# Sheet3.net
KiCad netlist of a schematic drawn in Altium Designer
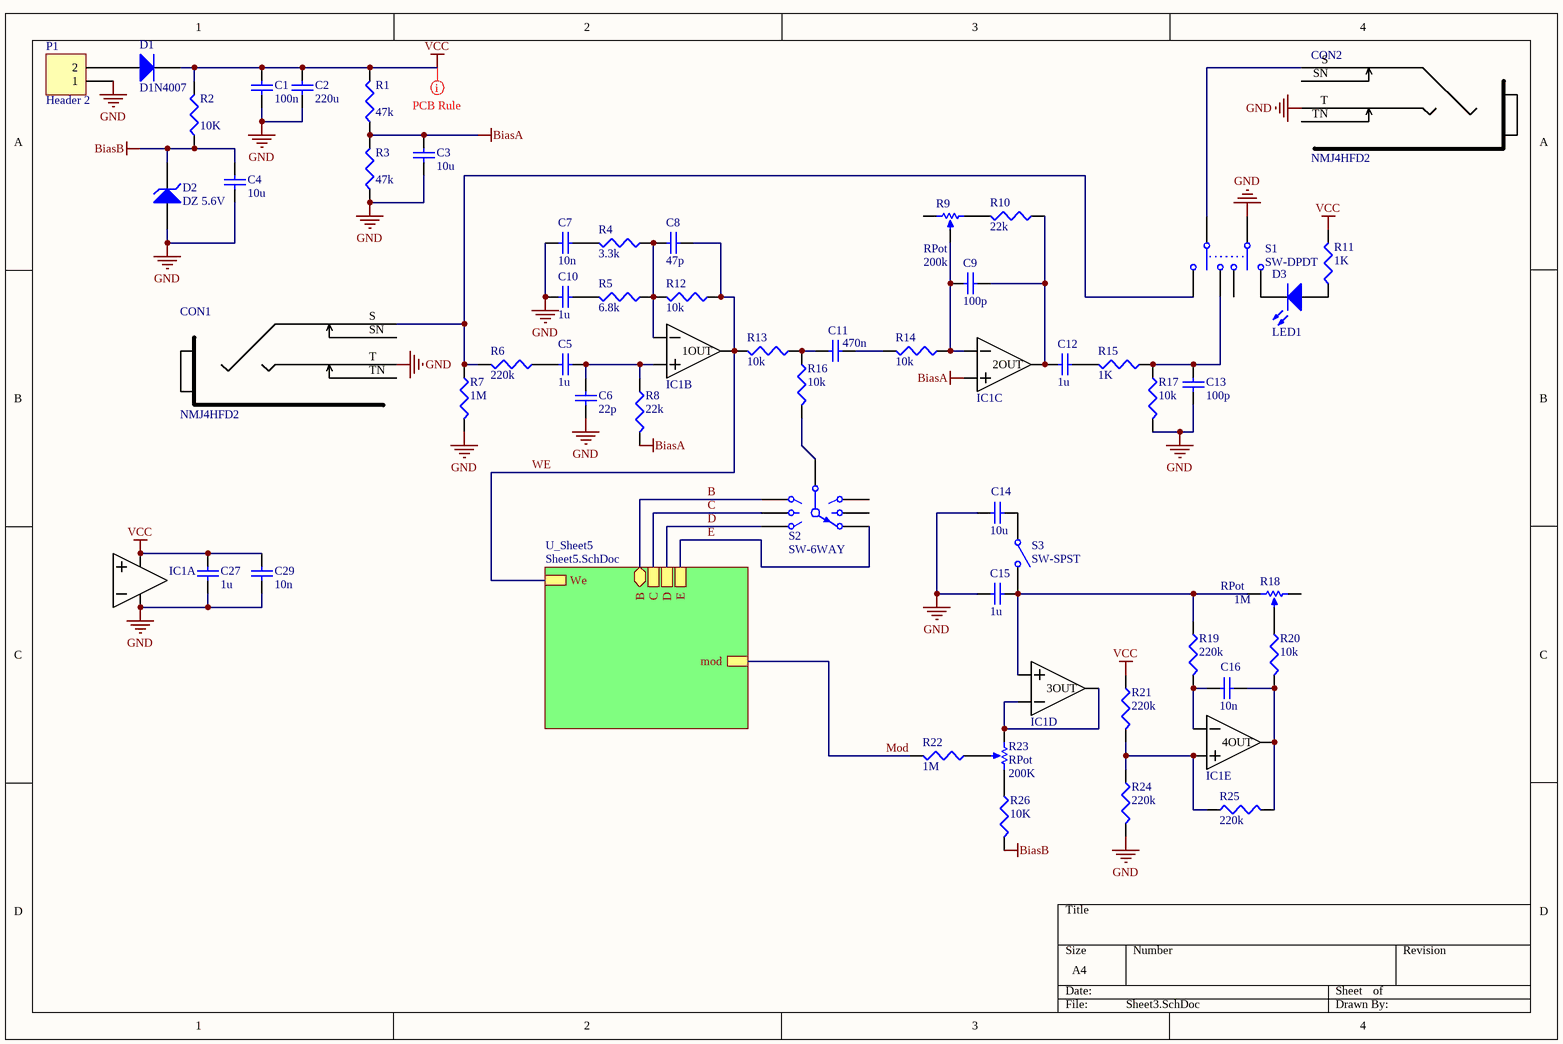
[diagram p0: Sheet3.SchDoc]

(export (version "E")
  (design (tool "Eeschema 10.0.6"))
  (components
    (comp (ref "C1")
      (value "100n")
      (footprint "C1206")
      (description "Capacitor (Semiconductor SIM Model)")
      (fields (field (name "Comment") "Cap Semi") (field (name "PUBLISHER") "Altium Limited"))
      (libsource (lib "Miscellaneous Devices") (part "Cap Semi"))
    )
    (comp (ref "C2")
      (value "220u")
      (footprint "C1206")
      (description "Capacitor (Semiconductor SIM Model)")
      (fields (field (name "Comment") "Cap Semi") (field (name "PUBLISHER") "Altium Limited"))
      (libsource (lib "Miscellaneous Devices") (part "Cap Semi"))
    )
    (comp (ref "C3")
      (value "10u")
      (footprint "C1206")
      (description "Capacitor (Semiconductor SIM Model)")
      (fields (field (name "Comment") "Cap Semi") (field (name "PUBLISHER") "Altium Limited"))
      (libsource (lib "Miscellaneous Devices") (part "Cap Semi"))
    )
    (comp (ref "C4")
      (value "10u")
      (footprint "C1206")
      (description "Capacitor (Semiconductor SIM Model)")
      (fields (field (name "Comment") "Cap Semi") (field (name "PUBLISHER") "Altium Limited"))
      (libsource (lib "Miscellaneous Devices") (part "Cap Semi"))
    )
    (comp (ref "C5")
      (value "1u")
      (footprint "C1206")
      (description "Capacitor (Semiconductor SIM Model)")
      (fields (field (name "Comment") "Cap Semi") (field (name "PUBLISHER") "Altium Limited"))
      (libsource (lib "Miscellaneous Devices") (part "Cap Semi"))
    )
    (comp (ref "C6")
      (value "22p")
      (footprint "C1206")
      (description "Capacitor (Semiconductor SIM Model)")
      (fields (field (name "Comment") "Cap Semi") (field (name "PUBLISHER") "Altium Limited"))
      (libsource (lib "Miscellaneous Devices") (part "Cap Semi"))
    )
    (comp (ref "C7")
      (value "10n")
      (footprint "C1206")
      (description "Capacitor (Semiconductor SIM Model)")
      (fields (field (name "Comment") "Cap Semi") (field (name "PUBLISHER") "Altium Limited"))
      (libsource (lib "Miscellaneous Devices") (part "Cap Semi"))
    )
    (comp (ref "C8")
      (value "47p")
      (footprint "C1206")
      (description "Capacitor (Semiconductor SIM Model)")
      (fields (field (name "Comment") "Cap Semi") (field (name "PUBLISHER") "Altium Limited"))
      (libsource (lib "Miscellaneous Devices") (part "Cap Semi"))
    )
    (comp (ref "C9")
      (value "100p")
      (footprint "C1206")
      (description "Capacitor (Semiconductor SIM Model)")
      (fields (field (name "Comment") "Cap Semi") (field (name "PUBLISHER") "Altium Limited"))
      (libsource (lib "Miscellaneous Devices") (part "Cap Semi"))
    )
    (comp (ref "C10")
      (value "1u")
      (footprint "C1206")
      (description "Capacitor (Semiconductor SIM Model)")
      (fields (field (name "Comment") "Cap Semi") (field (name "PUBLISHER") "Altium Limited"))
      (libsource (lib "Miscellaneous Devices") (part "Cap Semi"))
    )
    (comp (ref "C11")
      (value "470n")
      (footprint "C1206")
      (description "Capacitor (Semiconductor SIM Model)")
      (fields (field (name "Comment") "Cap Semi") (field (name "PUBLISHER") "Altium Limited"))
      (libsource (lib "Miscellaneous Devices") (part "Cap Semi"))
    )
    (comp (ref "C12")
      (value "1u")
      (footprint "C1206")
      (description "Capacitor (Semiconductor SIM Model)")
      (fields (field (name "Comment") "Cap Semi") (field (name "PUBLISHER") "Altium Limited"))
      (libsource (lib "Miscellaneous Devices") (part "Cap Semi"))
    )
    (comp (ref "C13")
      (value "100p")
      (footprint "C1206")
      (description "Capacitor (Semiconductor SIM Model)")
      (fields (field (name "Comment") "Cap Semi") (field (name "PUBLISHER") "Altium Limited"))
      (libsource (lib "Miscellaneous Devices") (part "Cap Semi"))
    )
    (comp (ref "C14")
      (value "10u")
      (footprint "C1206")
      (description "Capacitor (Semiconductor SIM Model)")
      (fields (field (name "Comment") "Cap Semi") (field (name "PUBLISHER") "Altium Limited"))
      (libsource (lib "Miscellaneous Devices") (part "Cap Semi"))
    )
    (comp (ref "C15")
      (value "1u")
      (footprint "C1206")
      (description "Capacitor (Semiconductor SIM Model)")
      (fields (field (name "Comment") "Cap Semi") (field (name "PUBLISHER") "Altium Limited"))
      (libsource (lib "Miscellaneous Devices") (part "Cap Semi"))
    )
    (comp (ref "C16")
      (value "10n")
      (footprint "C1206")
      (description "Capacitor (Semiconductor SIM Model)")
      (fields (field (name "Comment") "Cap Semi") (field (name "PUBLISHER") "Altium Limited"))
      (libsource (lib "Miscellaneous Devices") (part "Cap Semi"))
    )
    (comp (ref "C27")
      (value "1u")
      (footprint "C1206")
      (description "Capacitor (Semiconductor SIM Model)")
      (fields (field (name "Comment") "Cap Semi") (field (name "PUBLISHER") "Altium Limited"))
      (libsource (lib "Miscellaneous Devices") (part "Cap Semi"))
    )
    (comp (ref "C29")
      (value "10n")
      (footprint "C1206")
      (description "Capacitor (Semiconductor SIM Model)")
      (fields (field (name "Comment") "Cap Semi") (field (name "PUBLISHER") "Altium Limited"))
      (libsource (lib "Miscellaneous Devices") (part "Cap Semi"))
    )
    (comp (ref "CON1")
      (value "NMJ4HFD2")
      (footprint "NMJ4HFD2")
      (description "1/4\" jack connector")
      (libsource (lib "lib1") (part "NMJ4HFD2"))
    )
    (comp (ref "CON2")
      (value "NMJ4HFD2")
      (footprint "NMJ4HFD2")
      (description "1/4\" jack connector")
      (libsource (lib "lib1") (part "NMJ4HFD2"))
    )
    (comp (ref "D1")
      (value "D1N4007")
      (footprint "DO-41")
      (description "1 Amp General Purpose Rectifier")
      (fields (field (name "PUBLISHER") "Altium Limited"))
      (libsource (lib "Miscellaneous Devices") (part "Diode 1N4007"))
    )
    (comp (ref "D2")
      (value "DZ 5.6V")
      (footprint "DIODE-0.7")
      (description "Zener Diode")
      (fields (field (name "PUBLISHER") "Altium Limited"))
      (libsource (lib "Miscellaneous Devices") (part "D Zener"))
    )
    (comp (ref "D3")
      (value "LED1")
      (footprint "LED-1")
      (description "Typical RED GaAs LED")
      (fields (field (name "PUBLISHER") "Altium Limited"))
      (libsource (lib "Miscellaneous Devices") (part "LED1"))
    )
    (comp (ref "IC1")
      (value "TL074A")
      (footprint "TL074A")
      (description "TL074A Op-Amp")
      (libsource (lib "lib1") (part "TL074A"))
    )
    (comp (ref "P1")
      (value "Header 2")
      (footprint "HDR1X2")
      (description "Header, 2-Pin")
      (fields (field (name "PUBLISHER") "Altium Limited"))
      (libsource (lib "Miscellaneous Connectors") (part "Header 2"))
    )
    (comp (ref "R1")
      (value "47k")
      (footprint "J1-0603")
      (description "Resistor")
      (fields (field (name "Comment") "Res3") (field (name "PUBLISHER") "Altium Limited"))
      (libsource (lib "Miscellaneous Devices") (part "Res3"))
    )
    (comp (ref "R2")
      (value "10K")
      (footprint "J1-0603")
      (description "Resistor")
      (fields (field (name "Comment") "Res3") (field (name "PUBLISHER") "Altium Limited"))
      (libsource (lib "Miscellaneous Devices") (part "Res3"))
    )
    (comp (ref "R3")
      (value "47k")
      (footprint "J1-0603")
      (description "Resistor")
      (fields (field (name "Comment") "Res3") (field (name "PUBLISHER") "Altium Limited"))
      (libsource (lib "Miscellaneous Devices") (part "Res3"))
    )
    (comp (ref "R4")
      (value "3.3k")
      (footprint "J1-0603")
      (description "Resistor")
      (fields (field (name "Comment") "Res3") (field (name "PUBLISHER") "Altium Limited"))
      (libsource (lib "Miscellaneous Devices") (part "Res3"))
    )
    (comp (ref "R5")
      (value "6.8k")
      (footprint "J1-0603")
      (description "Resistor")
      (fields (field (name "Comment") "Res3") (field (name "PUBLISHER") "Altium Limited"))
      (libsource (lib "Miscellaneous Devices") (part "Res3"))
    )
    (comp (ref "R6")
      (value "220k")
      (footprint "J1-0603")
      (description "Resistor")
      (fields (field (name "Comment") "Res3") (field (name "PUBLISHER") "Altium Limited"))
      (libsource (lib "Miscellaneous Devices") (part "Res3"))
    )
    (comp (ref "R7")
      (value "1M")
      (footprint "J1-0603")
      (description "Resistor")
      (fields (field (name "Comment") "Res3") (field (name "PUBLISHER") "Altium Limited"))
      (libsource (lib "Miscellaneous Devices") (part "Res3"))
    )
    (comp (ref "R8")
      (value "22k")
      (footprint "J1-0603")
      (description "Resistor")
      (fields (field (name "Comment") "Res3") (field (name "PUBLISHER") "Altium Limited"))
      (libsource (lib "Miscellaneous Devices") (part "Res3"))
    )
    (comp (ref "R9")
      (value "RPot")
      (footprint "VR5")
      (description "Potentiometer")
      (fields (field (name "ALTIUM_VALUE") "200k") (field (name "PUBLISHER") "Altium Limited"))
      (libsource (lib "Miscellaneous Devices") (part "RPot"))
    )
    (comp (ref "R10")
      (value "22k")
      (footprint "J1-0603")
      (description "Resistor")
      (fields (field (name "Comment") "Res3") (field (name "PUBLISHER") "Altium Limited"))
      (libsource (lib "Miscellaneous Devices") (part "Res3"))
    )
    (comp (ref "R11")
      (value "1K")
      (footprint "J1-0603")
      (description "Resistor")
      (fields (field (name "Comment") "Res3") (field (name "PUBLISHER") "Altium Limited"))
      (libsource (lib "Miscellaneous Devices") (part "Res3"))
    )
    (comp (ref "R12")
      (value "10k")
      (footprint "J1-0603")
      (description "Resistor")
      (fields (field (name "Comment") "Res3") (field (name "PUBLISHER") "Altium Limited"))
      (libsource (lib "Miscellaneous Devices") (part "Res3"))
    )
    (comp (ref "R13")
      (value "10k")
      (footprint "J1-0603")
      (description "Resistor")
      (fields (field (name "Comment") "Res3") (field (name "PUBLISHER") "Altium Limited"))
      (libsource (lib "Miscellaneous Devices") (part "Res3"))
    )
    (comp (ref "R14")
      (value "10k")
      (footprint "J1-0603")
      (description "Resistor")
      (fields (field (name "Comment") "Res3") (field (name "PUBLISHER") "Altium Limited"))
      (libsource (lib "Miscellaneous Devices") (part "Res3"))
    )
    (comp (ref "R15")
      (value "1K")
      (footprint "J1-0603")
      (description "Resistor")
      (fields (field (name "Comment") "Res3") (field (name "PUBLISHER") "Altium Limited"))
      (libsource (lib "Miscellaneous Devices") (part "Res3"))
    )
    (comp (ref "R16")
      (value "10k")
      (footprint "J1-0603")
      (description "Resistor")
      (fields (field (name "Comment") "Res3") (field (name "PUBLISHER") "Altium Limited"))
      (libsource (lib "Miscellaneous Devices") (part "Res3"))
    )
    (comp (ref "R17")
      (value "10k")
      (footprint "J1-0603")
      (description "Resistor")
      (fields (field (name "Comment") "Res3") (field (name "PUBLISHER") "Altium Limited"))
      (libsource (lib "Miscellaneous Devices") (part "Res3"))
    )
    (comp (ref "R18")
      (value "RPot")
      (footprint "VR5")
      (description "Potentiometer")
      (fields (field (name "ALTIUM_VALUE") "1M") (field (name "PUBLISHER") "Altium Limited"))
      (libsource (lib "Miscellaneous Devices") (part "RPot"))
    )
    (comp (ref "R19")
      (value "220k")
      (footprint "J1-0603")
      (description "Resistor")
      (fields (field (name "Comment") "Res3") (field (name "PUBLISHER") "Altium Limited"))
      (libsource (lib "Miscellaneous Devices") (part "Res3"))
    )
    (comp (ref "R20")
      (value "10k")
      (footprint "J1-0603")
      (description "Resistor")
      (fields (field (name "Comment") "Res3") (field (name "PUBLISHER") "Altium Limited"))
      (libsource (lib "Miscellaneous Devices") (part "Res3"))
    )
    (comp (ref "R21")
      (value "220k")
      (footprint "J1-0603")
      (description "Resistor")
      (fields (field (name "Comment") "Res3") (field (name "PUBLISHER") "Altium Limited"))
      (libsource (lib "Miscellaneous Devices") (part "Res3"))
    )
    (comp (ref "R22")
      (value "1M")
      (footprint "J1-0603")
      (description "Resistor")
      (fields (field (name "Comment") "Res3") (field (name "PUBLISHER") "Altium Limited"))
      (libsource (lib "Miscellaneous Devices") (part "Res3"))
    )
    (comp (ref "R23")
      (value "RPot")
      (footprint "VR5")
      (description "Potentiometer")
      (fields (field (name "ALTIUM_VALUE") "200K") (field (name "PUBLISHER") "Altium Limited"))
      (libsource (lib "Miscellaneous Devices") (part "RPot"))
    )
    (comp (ref "R24")
      (value "220k")
      (footprint "J1-0603")
      (description "Resistor")
      (fields (field (name "Comment") "Res3") (field (name "PUBLISHER") "Altium Limited"))
      (libsource (lib "Miscellaneous Devices") (part "Res3"))
    )
    (comp (ref "R25")
      (value "220k")
      (footprint "J1-0603")
      (description "Resistor")
      (fields (field (name "Comment") "Res3") (field (name "PUBLISHER") "Altium Limited"))
      (libsource (lib "Miscellaneous Devices") (part "Res3"))
    )
    (comp (ref "R26")
      (value "10K")
      (footprint "J1-0603")
      (description "Resistor")
      (fields (field (name "Comment") "Res3") (field (name "PUBLISHER") "Altium Limited"))
      (libsource (lib "Miscellaneous Devices") (part "Res3"))
    )
    (comp (ref "S1")
      (value "SW-DPDT")
      (footprint "DPDT-6")
      (description "Double-Pole, Double-Throw Switch")
      (fields (field (name "PUBLISHER") "Altium Limited"))
      (libsource (lib "Miscellaneous Devices") (part "SW-DPDT"))
    )
    (comp (ref "S2")
      (value "SW-6WAY")
      (footprint "SW-7")
      (description "6 Way Switch")
      (fields (field (name "PUBLISHER") "Altium Limited"))
      (libsource (lib "Miscellaneous Devices") (part "SW-6WAY"))
    )
    (comp (ref "S3")
      (value "SW-SPST")
      (footprint "SPST-2")
      (description "Single-Pole, Single-Throw Switch")
      (fields (field (name "PUBLISHER") "Altium Limited"))
      (libsource (lib "Miscellaneous Devices") (part "SW-SPST"))
    )
  )
  (nets
    (net (code "1") (name "/B") (class "Default")
      (node (ref "S2") (pin "1") (pinfunction "1_1") (pintype "passive"))
    )
    (net (code "2") (name "/C") (class "Default")
      (node (ref "S2") (pin "2") (pinfunction "2_2") (pintype "passive"))
    )
    (net (code "3") (name "/D") (class "Default")
      (node (ref "S2") (pin "3") (pinfunction "3_3") (pintype "passive"))
    )
    (net (code "4") (name "/E") (class "Default")
      (node (ref "S2") (pin "6") (pinfunction "6_6") (pintype "passive"))
    )
    (net (code "5") (name "/Mod") (class "Default")
      (node (ref "R22") (pin "2") (pinfunction "2_2") (pintype "passive"))
    )
    (net (code "6") (name "/WE") (class "Default")
      (node (ref "C8") (pin "1") (pinfunction "1_1") (pintype "passive"))
      (node (ref "IC1") (pin "1") (pinfunction "1OUT_1") (pintype "passive"))
      (node (ref "R12") (pin "1") (pinfunction "1_1") (pintype "passive"))
      (node (ref "R13") (pin "2") (pinfunction "2_2") (pintype "passive"))
    )
    (net (code "7") (name "BiasA") (class "Default")
      (node (ref "C3") (pin "2") (pinfunction "2_2") (pintype "passive"))
      (node (ref "IC1") (pin "5") (pinfunction "2IN+_5") (pintype "passive"))
      (node (ref "R1") (pin "1") (pinfunction "1_1") (pintype "passive"))
      (node (ref "R3") (pin "2") (pinfunction "2_2") (pintype "passive"))
      (node (ref "R8") (pin "2") (pinfunction "2_2") (pintype "passive"))
    )
    (net (code "8") (name "BiasB") (class "Default")
      (node (ref "C4") (pin "2") (pinfunction "2_2") (pintype "passive"))
      (node (ref "D2") (pin "2") (pinfunction "K_2") (pintype "passive"))
      (node (ref "R2") (pin "1") (pinfunction "1_1") (pintype "passive"))
      (node (ref "R26") (pin "2") (pinfunction "2_2") (pintype "passive"))
    )
    (net (code "9") (name "GND") (class "Default")
      (node (ref "C1") (pin "1") (pinfunction "1_1") (pintype "passive"))
      (node (ref "C10") (pin "2") (pinfunction "2_2") (pintype "passive"))
      (node (ref "C13") (pin "2") (pinfunction "2_2") (pintype "passive"))
      (node (ref "C14") (pin "1") (pinfunction "1_1") (pintype "passive"))
      (node (ref "C15") (pin "1") (pinfunction "1_1") (pintype "passive"))
      (node (ref "C2") (pin "1") (pinfunction "1_1") (pintype "passive"))
      (node (ref "C27") (pin "1") (pinfunction "1_1") (pintype "passive"))
      (node (ref "C29") (pin "1") (pinfunction "1_1") (pintype "passive"))
      (node (ref "C3") (pin "1") (pinfunction "1_1") (pintype "passive"))
      (node (ref "C4") (pin "1") (pinfunction "1_1") (pintype "passive"))
      (node (ref "C6") (pin "2") (pinfunction "2_2") (pintype "passive"))
      (node (ref "C7") (pin "2") (pinfunction "2_2") (pintype "passive"))
      (node (ref "CON1") (pin "T") (pinfunction "T_T") (pintype "passive"))
      (node (ref "CON2") (pin "T") (pinfunction "T_T") (pintype "passive"))
      (node (ref "D2") (pin "1") (pinfunction "A_1") (pintype "passive"))
      (node (ref "IC1") (pin "11") (pinfunction "VCC-_11") (pintype "passive"))
      (node (ref "P1") (pin "1") (pinfunction "1_1") (pintype "passive"))
      (node (ref "R17") (pin "2") (pinfunction "2_2") (pintype "passive"))
      (node (ref "R24") (pin "2") (pinfunction "2_2") (pintype "passive"))
      (node (ref "R3") (pin "1") (pinfunction "1_1") (pintype "passive"))
      (node (ref "R7") (pin "2") (pinfunction "2_2") (pintype "passive"))
      (node (ref "S1") (pin "1") (pinfunction "1_1") (pintype "passive"))
    )
    (net (code "10") (name "Net-(C5-Pad2)") (class "Default")
      (node (ref "C5") (pin "2") (pinfunction "2_2") (pintype "passive"))
      (node (ref "R6") (pin "1") (pinfunction "1_1") (pintype "passive"))
    )
    (net (code "11") (name "Net-(C7-Pad1)") (class "Default")
      (node (ref "C7") (pin "1") (pinfunction "1_1") (pintype "passive"))
      (node (ref "R4") (pin "2") (pinfunction "2_2") (pintype "passive"))
    )
    (net (code "12") (name "Net-(C10-Pad1)") (class "Default")
      (node (ref "C10") (pin "1") (pinfunction "1_1") (pintype "passive"))
      (node (ref "R5") (pin "2") (pinfunction "2_2") (pintype "passive"))
    )
    (net (code "13") (name "Net-(C11-Pad1)") (class "Default")
      (node (ref "C11") (pin "1") (pinfunction "1_1") (pintype "passive"))
      (node (ref "R14") (pin "2") (pinfunction "2_2") (pintype "passive"))
    )
    (net (code "14") (name "Net-(C11-Pad2)") (class "Default")
      (node (ref "C11") (pin "2") (pinfunction "2_2") (pintype "passive"))
      (node (ref "R13") (pin "1") (pinfunction "1_1") (pintype "passive"))
      (node (ref "R16") (pin "1") (pinfunction "1_1") (pintype "passive"))
    )
    (net (code "15") (name "Net-(C12-Pad1)") (class "Default")
      (node (ref "C12") (pin "1") (pinfunction "1_1") (pintype "passive"))
      (node (ref "R15") (pin "2") (pinfunction "2_2") (pintype "passive"))
    )
    (net (code "16") (name "Net-(C13-Pad1)") (class "Default")
      (node (ref "C13") (pin "1") (pinfunction "1_1") (pintype "passive"))
      (node (ref "R15") (pin "1") (pinfunction "1_1") (pintype "passive"))
      (node (ref "R17") (pin "1") (pinfunction "1_1") (pintype "passive"))
      (node (ref "S1") (pin "5") (pinfunction "5_5") (pintype "passive"))
    )
    (net (code "17") (name "Net-(CON1-PadS)") (class "Default")
      (node (ref "CON1") (pin "S") (pinfunction "S_S") (pintype "passive"))
      (node (ref "R6") (pin "2") (pinfunction "2_2") (pintype "passive"))
      (node (ref "R7") (pin "1") (pinfunction "1_1") (pintype "passive"))
      (node (ref "S1") (pin "6") (pinfunction "6_6") (pintype "passive"))
    )
    (net (code "18") (name "Net-(CON2-PadS)") (class "Default")
      (node (ref "CON2") (pin "S") (pinfunction "S_S") (pintype "passive"))
      (node (ref "S1") (pin "4") (pinfunction "4_4") (pintype "passive"))
    )
    (net (code "19") (name "Net-(D1-A)") (class "Default")
      (node (ref "D1") (pin "1") (pinfunction "A_1") (pintype "passive"))
      (node (ref "P1") (pin "2") (pinfunction "2_2") (pintype "passive"))
    )
    (net (code "20") (name "Net-(D3-A)") (class "Default")
      (node (ref "D3") (pin "1") (pinfunction "A_1") (pintype "passive"))
      (node (ref "R11") (pin "1") (pinfunction "1_1") (pintype "passive"))
    )
    (net (code "21") (name "Net-(D3-K)") (class "Default")
      (node (ref "D3") (pin "2") (pinfunction "K_2") (pintype "passive"))
      (node (ref "S1") (pin "2") (pinfunction "2_2") (pintype "passive"))
    )
    (net (code "22") (name "Net-(IC1B-1IN+)") (class "Default")
      (node (ref "C5") (pin "1") (pinfunction "1_1") (pintype "passive"))
      (node (ref "C6") (pin "1") (pinfunction "1_1") (pintype "passive"))
      (node (ref "IC1") (pin "3") (pinfunction "1IN+_3") (pintype "passive"))
      (node (ref "R8") (pin "1") (pinfunction "1_1") (pintype "passive"))
    )
    (net (code "23") (name "Net-(IC1B-1IN-)") (class "Default")
      (node (ref "C8") (pin "2") (pinfunction "2_2") (pintype "passive"))
      (node (ref "IC1") (pin "2") (pinfunction "1IN-_2") (pintype "passive"))
      (node (ref "R12") (pin "2") (pinfunction "2_2") (pintype "passive"))
      (node (ref "R4") (pin "1") (pinfunction "1_1") (pintype "passive"))
      (node (ref "R5") (pin "1") (pinfunction "1_1") (pintype "passive"))
    )
    (net (code "24") (name "Net-(IC1C-2IN-)") (class "Default")
      (node (ref "C9") (pin "2") (pinfunction "2_2") (pintype "passive"))
      (node (ref "IC1") (pin "6") (pinfunction "2IN-_6") (pintype "passive"))
      (node (ref "R14") (pin "1") (pinfunction "1_1") (pintype "passive"))
      (node (ref "R9") (pin "3") (pinfunction "TAP_3") (pintype "passive"))
    )
    (net (code "25") (name "Net-(IC1C-2OUT)") (class "Default")
      (node (ref "C12") (pin "2") (pinfunction "2_2") (pintype "passive"))
      (node (ref "C9") (pin "1") (pinfunction "1_1") (pintype "passive"))
      (node (ref "IC1") (pin "7") (pinfunction "2OUT_7") (pintype "passive"))
      (node (ref "R10") (pin "1") (pinfunction "1_1") (pintype "passive"))
    )
    (net (code "26") (name "Net-(IC1D-3IN+)") (class "Default")
      (node (ref "C15") (pin "2") (pinfunction "2_2") (pintype "passive"))
      (node (ref "IC1") (pin "10") (pinfunction "3IN+_10") (pintype "passive"))
      (node (ref "R18") (pin "1") (pinfunction "TOP_1") (pintype "passive"))
      (node (ref "R19") (pin "1") (pinfunction "1_1") (pintype "passive"))
      (node (ref "S3") (pin "2") (pinfunction "NO_2") (pintype "passive"))
    )
    (net (code "27") (name "Net-(IC1D-3IN-)") (class "Default")
      (node (ref "IC1") (pin "8") (pinfunction "3OUT_8") (pintype "passive"))
      (node (ref "IC1") (pin "9") (pinfunction "3IN-_9") (pintype "passive"))
      (node (ref "R23") (pin "1") (pinfunction "TOP_1") (pintype "passive"))
    )
    (net (code "28") (name "Net-(IC1E-4IN+)") (class "Default")
      (node (ref "IC1") (pin "12") (pinfunction "4IN+_12") (pintype "passive"))
      (node (ref "R21") (pin "2") (pinfunction "2_2") (pintype "passive"))
      (node (ref "R24") (pin "1") (pinfunction "1_1") (pintype "passive"))
      (node (ref "R25") (pin "1") (pinfunction "1_1") (pintype "passive"))
    )
    (net (code "29") (name "Net-(IC1E-4IN-)") (class "Default")
      (node (ref "C16") (pin "1") (pinfunction "1_1") (pintype "passive"))
      (node (ref "IC1") (pin "13") (pinfunction "4IN-_13") (pintype "passive"))
      (node (ref "R19") (pin "2") (pinfunction "2_2") (pintype "passive"))
    )
    (net (code "30") (name "Net-(IC1E-4OUT)") (class "Default")
      (node (ref "C16") (pin "2") (pinfunction "2_2") (pintype "passive"))
      (node (ref "IC1") (pin "14") (pinfunction "4OUT_14") (pintype "passive"))
      (node (ref "R20") (pin "2") (pinfunction "2_2") (pintype "passive"))
      (node (ref "R25") (pin "2") (pinfunction "2_2") (pintype "passive"))
    )
    (net (code "31") (name "Net-(R9-BOT)") (class "Default")
      (node (ref "R10") (pin "2") (pinfunction "2_2") (pintype "passive"))
      (node (ref "R9") (pin "2") (pinfunction "BOT_2") (pintype "passive"))
    )
    (net (code "32") (name "Net-(R16-Pad2)") (class "Default")
      (node (ref "R16") (pin "2") (pinfunction "2_2") (pintype "passive"))
      (node (ref "S2") (pin "7") (pinfunction "7_7") (pintype "passive"))
    )
    (net (code "33") (name "Net-(R18-TAP)") (class "Default")
      (node (ref "R18") (pin "3") (pinfunction "TAP_3") (pintype "passive"))
      (node (ref "R20") (pin "1") (pinfunction "1_1") (pintype "passive"))
    )
    (net (code "34") (name "Net-(R23-BOT)") (class "Default")
      (node (ref "R23") (pin "2") (pinfunction "BOT_2") (pintype "passive"))
      (node (ref "R26") (pin "1") (pinfunction "1_1") (pintype "passive"))
    )
    (net (code "35") (name "Net-(R23-TAP)") (class "Default")
      (node (ref "R22") (pin "1") (pinfunction "1_1") (pintype "passive"))
      (node (ref "R23") (pin "3") (pinfunction "TAP_3") (pintype "passive"))
    )
    (net (code "36") (name "Net-(S3-COMMON)") (class "Default")
      (node (ref "C14") (pin "2") (pinfunction "2_2") (pintype "passive"))
      (node (ref "S3") (pin "1") (pinfunction "COMMON_1") (pintype "passive"))
    )
    (net (code "37") (name "VCC") (class "Default")
      (node (ref "C1") (pin "2") (pinfunction "2_2") (pintype "passive"))
      (node (ref "C2") (pin "2") (pinfunction "2_2") (pintype "passive"))
      (node (ref "C27") (pin "2") (pinfunction "2_2") (pintype "passive"))
      (node (ref "C29") (pin "2") (pinfunction "2_2") (pintype "passive"))
      (node (ref "D1") (pin "2") (pinfunction "K_2") (pintype "passive"))
      (node (ref "IC1") (pin "4") (pinfunction "VCC+_4") (pintype "passive"))
      (node (ref "R1") (pin "2") (pinfunction "2_2") (pintype "passive"))
      (node (ref "R11") (pin "2") (pinfunction "2_2") (pintype "passive"))
      (node (ref "R2") (pin "2") (pinfunction "2_2") (pintype "passive"))
      (node (ref "R21") (pin "1") (pinfunction "1_1") (pintype "passive"))
    )
    (net (code "38") (name "unconnected-(CON1-PadSN)") (class "Default")
      (node (ref "CON1") (pin "SN") (pinfunction "SN_SN") (pintype "passive"))
    )
    (net (code "39") (name "unconnected-(CON1-PadTN)") (class "Default")
      (node (ref "CON1") (pin "TN") (pinfunction "TN_TN") (pintype "passive"))
    )
    (net (code "40") (name "unconnected-(CON2-PadSN)") (class "Default")
      (node (ref "CON2") (pin "SN") (pinfunction "SN_SN") (pintype "passive"))
    )
    (net (code "41") (name "unconnected-(CON2-PadTN)") (class "Default")
      (node (ref "CON2") (pin "TN") (pinfunction "TN_TN") (pintype "passive"))
    )
    (net (code "42") (name "unconnected-(R9-TOP-Pad1)") (class "Default")
      (node (ref "R9") (pin "1") (pinfunction "TOP_1") (pintype "passive"))
    )
    (net (code "43") (name "unconnected-(R18-BOT-Pad2)") (class "Default")
      (node (ref "R18") (pin "2") (pinfunction "BOT_2") (pintype "passive"))
    )
    (net (code "44") (name "unconnected-(S1-Pad3)") (class "Default")
      (node (ref "S1") (pin "3") (pinfunction "3_3") (pintype "passive"))
    )
    (net (code "45") (name "unconnected-(S2-Pad4)") (class "Default")
      (node (ref "S2") (pin "4") (pinfunction "4_4") (pintype "passive"))
    )
    (net (code "46") (name "unconnected-(S2-Pad5)") (class "Default")
      (node (ref "S2") (pin "5") (pinfunction "5_5") (pintype "passive"))
    )
  )
)
